# MedicalSheet.net
KiCad netlist of a schematic drawn in Altium Designer
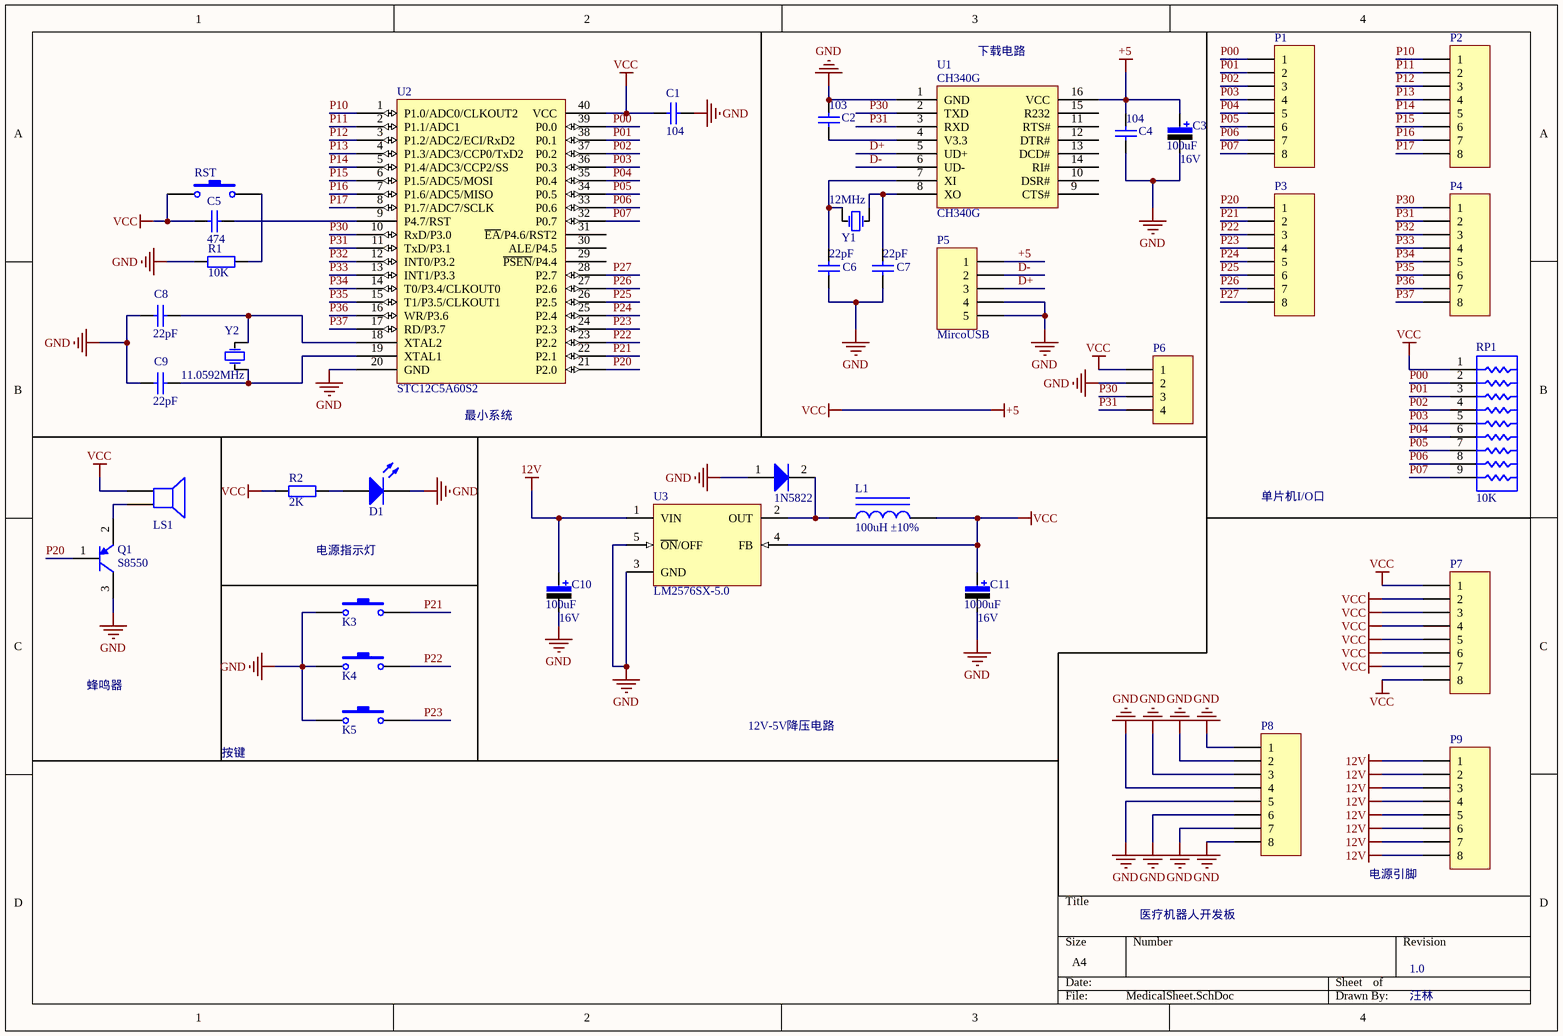
[diagram p0: MedicalSheet.SchDoc]

(export (version "E")
  (design (tool "Eeschema 10.0.6"))
  (components
    (comp (ref "1N5822")
      (value "Diode_SMA_S")
      (footprint "SMA(DO-214AC)_S1")
      (description "SMA")
      (libsource (lib "Miscellaneous_Devices_ZSF_Library") (part "Diode_SMA_S"))
    )
    (comp (ref "C1")
      (value "104")
      (footprint "C-RAD-0805")
      (description "无极性电容")
      (fields (field (name "Comment") "Cap") (field (name "PUBLISHER") "Altium Limited"))
      (libsource (lib "Fszhang") (part "Cap"))
    )
    (comp (ref "C2")
      (value "103")
      (footprint "C-RAD-0805")
      (description "无极性电容")
      (fields (field (name "Comment") "Cap") (field (name "PUBLISHER") "Altium Limited"))
      (libsource (lib "Fszhang") (part "Cap"))
    )
    (comp (ref "C3")
      (value "100uF")
      (footprint "C-RB-8")
      (description "极性电解电容")
      (fields
        (field (name "VOL") "16V")
        (field (name "Comment") "Cap Pol")
        (field (name "PUBLISHER") "Altium Limited")
      )
      (libsource (lib "Fszhang") (part "Cap Pol"))
    )
    (comp (ref "C4")
      (value "104")
      (footprint "C-RAD-0805")
      (description "无极性电容")
      (fields (field (name "Comment") "Cap") (field (name "PUBLISHER") "Altium Limited"))
      (libsource (lib "Fszhang") (part "Cap"))
    )
    (comp (ref "C5")
      (value "474")
      (footprint "C-RAD-0805")
      (description "无极性电容")
      (fields (field (name "Comment") "Cap") (field (name "PUBLISHER") "Altium Limited"))
      (libsource (lib "Fszhang") (part "Cap"))
    )
    (comp (ref "C6")
      (value "22pF")
      (footprint "C-RAD-0805")
      (description "无极性电容")
      (fields (field (name "Comment") "Cap") (field (name "PUBLISHER") "Altium Limited"))
      (libsource (lib "Fszhang") (part "Cap"))
    )
    (comp (ref "C7")
      (value "22pF")
      (footprint "C-RAD-0805")
      (description "无极性电容")
      (fields (field (name "Comment") "Cap") (field (name "PUBLISHER") "Altium Limited"))
      (libsource (lib "Fszhang") (part "Cap"))
    )
    (comp (ref "C8")
      (value "22pF")
      (footprint "C-RAD-0805")
      (description "无极性电容")
      (fields (field (name "Comment") "Cap") (field (name "PUBLISHER") "Altium Limited"))
      (libsource (lib "Fszhang") (part "Cap"))
    )
    (comp (ref "C9")
      (value "22pF")
      (footprint "C-RAD-0805")
      (description "无极性电容")
      (fields (field (name "Comment") "Cap") (field (name "PUBLISHER") "Altium Limited"))
      (libsource (lib "Fszhang") (part "Cap"))
    )
    (comp (ref "C10")
      (value "100uF")
      (footprint "C-RB-8")
      (description "极性电解电容")
      (fields
        (field (name "VOL") "16V")
        (field (name "Comment") "Cap Pol")
        (field (name "PUBLISHER") "Altium Limited")
      )
      (libsource (lib "Fszhang") (part "Cap Pol"))
    )
    (comp (ref "C11")
      (value "1000uF")
      (footprint "C-RB-8")
      (description "极性电解电容")
      (fields
        (field (name "VOL") "16V")
        (field (name "Comment") "Cap Pol")
        (field (name "PUBLISHER") "Altium Limited")
      )
      (libsource (lib "Fszhang") (part "Cap Pol"))
    )
    (comp (ref "D1")
      (value "LED0")
      (footprint "LED3")
      (description "发光二极管")
      (fields (field (name "PUBLISHER") "Altium Limited"))
      (libsource (lib "PCB_One") (part "LED0"))
    )
    (comp (ref "K3")
      (value "Switch1")
      (footprint "SW_PB - 6.5x4.5")
      (description "按键/单刀单掷开关")
      (libsource (lib "PCB_One") (part "Switch1"))
    )
    (comp (ref "K4")
      (value "Switch1")
      (footprint "SW_PB - 6.5x4.5")
      (description "按键/单刀单掷开关")
      (libsource (lib "PCB_One") (part "Switch1"))
    )
    (comp (ref "K5")
      (value "Switch1")
      (footprint "SW_PB - 6.5x4.5")
      (description "按键/单刀单掷开关")
      (libsource (lib "PCB_One") (part "Switch1"))
    )
    (comp (ref "L1")
      (value "100uH ±10%")
      (footprint "0805_L")
      (description "贴片电感")
      (libsource (lib "Miscellaneous_Devices_ZSF_Library") (part "0805 100uH 10%"))
    )
    (comp (ref "LS1") (value "SPEAKER") (footprint "Beep") (libsource (lib "PCB_One") (part "SPEAKER")))
    (comp (ref "P1")
      (value "Header 8")
      (footprint "SIP8 - duplicate")
      (description "8PIN")
      (libsource (lib "PCB_One") (part "Header 8"))
    )
    (comp (ref "P2")
      (value "Header 8")
      (footprint "SIP8 - duplicate")
      (description "8PIN")
      (libsource (lib "PCB_One") (part "Header 8"))
    )
    (comp (ref "P3")
      (value "Header 8")
      (footprint "SIP8 - duplicate")
      (description "8PIN")
      (libsource (lib "PCB_One") (part "Header 8"))
    )
    (comp (ref "P4")
      (value "Header 8")
      (footprint "SIP8 - duplicate")
      (description "8PIN")
      (libsource (lib "PCB_One") (part "Header 8"))
    )
    (comp (ref "P5")
      (value "MircoUSB")
      (footprint "MircoUSB")
      (description "5PIN")
      (libsource (lib "PCB_One") (part "Header 5"))
    )
    (comp (ref "P6")
      (value "Header 4")
      (footprint "HDR4X1_A")
      (description "接插件")
      (fields (field (name "PUBLISHER") "Altium Limited"))
      (libsource (lib "Fszhang") (part "Header 4"))
    )
    (comp (ref "P7")
      (value "Header 8")
      (footprint "SIP8 - duplicate")
      (description "8PIN")
      (libsource (lib "PCB_One") (part "Header 8"))
    )
    (comp (ref "P8")
      (value "Header 8")
      (footprint "SIP8 - duplicate")
      (description "8PIN")
      (libsource (lib "PCB_One") (part "Header 8"))
    )
    (comp (ref "P9")
      (value "Header 8")
      (footprint "SIP8 - duplicate")
      (description "8PIN")
      (libsource (lib "PCB_One") (part "Header 8"))
    )
    (comp (ref "Q1")
      (value "S8550")
      (footprint "SOT-23")
      (description "PNP贴片三极管")
      (fields (field (name "PUBLISHER") "Altium Limited"))
      (libsource (lib "Fszhang") (part "SS8550"))
    )
    (comp (ref "R1")
      (value "10K")
      (footprint "0805-1")
      (description "贴片电阻")
      (fields (field (name "Comment") "Res1") (field (name "PUBLISHER") "Altium Limited"))
      (libsource (lib "Fszhang") (part "Res1"))
    )
    (comp (ref "R2")
      (value "2K")
      (footprint "0805-1")
      (description "贴片电阻")
      (fields (field (name "Comment") "Res1") (field (name "PUBLISHER") "Altium Limited"))
      (libsource (lib "Fszhang") (part "Res1"))
    )
    (comp (ref "RP1")
      (value "10K")
      (footprint "SIP9 - duplicate")
      (description "9PIN排阻")
      (libsource (lib "PCB_One") (part "Res Pack2"))
    )
    (comp (ref "RST")
      (value "Switch1")
      (footprint "SW_PB - 6.5x4.5")
      (description "按键/单刀单掷开关")
      (libsource (lib "PCB_One") (part "Switch1"))
    )
    (comp (ref "U1")
      (value "CH340G")
      (footprint "SOIC-16_150mil")
      (description "USB")
      (libsource (lib "Miscellaneous_Devices_ZSF_Library") (part "CH340G"))
    )
    (comp (ref "U2")
      (value "STC12C5A60S2")
      (footprint "DIP-40")
      (description "STC12C5A60S2_DIP")
      (libsource (lib "Miscellaneous_Devices_ZSF_Library") (part "STC12C5A60S2_DIP"))
    )
    (comp (ref "U3")
      (value "LM2576SX-5.0")
      (footprint "TO-263-5")
      (description "DC-DC芯片")
      (libsource (lib "Miscellaneous_Devices_ZSF_Library") (part "LM2576SX-5.0"))
    )
    (comp (ref "Y1")
      (value "12MHz")
      (footprint "XTAL1")
      (description "晶振")
      (fields (field (name "Comment") "XTAL") (field (name "PUBLISHER") "Altium Limited"))
      (libsource (lib "PCB_One") (part "XTAL"))
    )
    (comp (ref "Y2")
      (value "11.0592MHz")
      (footprint "XTAL1")
      (description "晶振")
      (fields (field (name "Comment") "XTAL") (field (name "PUBLISHER") "Altium Limited"))
      (libsource (lib "PCB_One") (part "XTAL"))
    )
  )
  (nets
    (net (code "1") (name "+5") (class "Default")
      (node (ref "C1") (pin "1") (pinfunction "1_1") (pintype "passive"))
      (node (ref "C11") (pin "1") (pinfunction "1_1") (pintype "passive"))
      (node (ref "C3") (pin "1") (pinfunction "1_1") (pintype "passive"))
      (node (ref "C4") (pin "2") (pinfunction "2_2") (pintype "passive"))
      (node (ref "C5") (pin "1") (pinfunction "1_1") (pintype "passive"))
      (node (ref "L1") (pin "2") (pinfunction "2_2") (pintype "passive"))
      (node (ref "LS1") (pin "1") (pinfunction "1_1") (pintype "passive"))
      (node (ref "P5") (pin "1") (pinfunction "1_1") (pintype "passive"))
      (node (ref "P6") (pin "1") (pinfunction "1_1") (pintype "passive"))
      (node (ref "P7") (pin "1") (pinfunction "1_1") (pintype "passive"))
      (node (ref "P7") (pin "2") (pinfunction "2_2") (pintype "passive"))
      (node (ref "P7") (pin "3") (pinfunction "3_3") (pintype "passive"))
      (node (ref "P7") (pin "4") (pinfunction "4_4") (pintype "passive"))
      (node (ref "P7") (pin "5") (pinfunction "5_5") (pintype "passive"))
      (node (ref "P7") (pin "6") (pinfunction "6_6") (pintype "passive"))
      (node (ref "P7") (pin "7") (pinfunction "7_7") (pintype "passive"))
      (node (ref "P7") (pin "8") (pinfunction "8_8") (pintype "passive"))
      (node (ref "R2") (pin "1") (pinfunction "1_1") (pintype "passive"))
      (node (ref "RP1") (pin "1") (pinfunction "1_1") (pintype "passive"))
      (node (ref "RST") (pin "1") (pinfunction "1_1") (pintype "passive"))
      (node (ref "U1") (pin "16") (pinfunction "VCC_16") (pintype "passive"))
      (node (ref "U2") (pin "40") (pinfunction "VCC_40") (pintype "power_in"))
      (node (ref "U3") (pin "4") (pinfunction "FB_4") (pintype "input"))
    )
    (net (code "2") (name "/D+") (class "Default")
      (node (ref "P5") (pin "3") (pinfunction "3_3") (pintype "passive"))
      (node (ref "U1") (pin "5") (pinfunction "UD+_5") (pintype "passive"))
    )
    (net (code "3") (name "/D-") (class "Default")
      (node (ref "P5") (pin "2") (pinfunction "2_2") (pintype "passive"))
      (node (ref "U1") (pin "6") (pinfunction "UD-_6") (pintype "passive"))
    )
    (net (code "4") (name "/P00") (class "Default")
      (node (ref "P1") (pin "1") (pinfunction "1_1") (pintype "passive"))
      (node (ref "RP1") (pin "2") (pinfunction "2_2") (pintype "passive"))
      (node (ref "U2") (pin "39") (pinfunction "P0.0_39") (pintype "bidirectional"))
    )
    (net (code "5") (name "/P01") (class "Default")
      (node (ref "P1") (pin "2") (pinfunction "2_2") (pintype "passive"))
      (node (ref "RP1") (pin "3") (pinfunction "3_3") (pintype "passive"))
      (node (ref "U2") (pin "38") (pinfunction "P0.1_38") (pintype "bidirectional"))
    )
    (net (code "6") (name "/P02") (class "Default")
      (node (ref "P1") (pin "3") (pinfunction "3_3") (pintype "passive"))
      (node (ref "RP1") (pin "4") (pinfunction "4_4") (pintype "passive"))
      (node (ref "U2") (pin "37") (pinfunction "P0.2_37") (pintype "bidirectional"))
    )
    (net (code "7") (name "/P03") (class "Default")
      (node (ref "P1") (pin "4") (pinfunction "4_4") (pintype "passive"))
      (node (ref "RP1") (pin "5") (pinfunction "5_5") (pintype "passive"))
      (node (ref "U2") (pin "36") (pinfunction "P0.3_36") (pintype "bidirectional"))
    )
    (net (code "8") (name "/P04") (class "Default")
      (node (ref "P1") (pin "5") (pinfunction "5_5") (pintype "passive"))
      (node (ref "RP1") (pin "6") (pinfunction "6_6") (pintype "passive"))
      (node (ref "U2") (pin "35") (pinfunction "P0.4_35") (pintype "bidirectional"))
    )
    (net (code "9") (name "/P05") (class "Default")
      (node (ref "P1") (pin "6") (pinfunction "6_6") (pintype "passive"))
      (node (ref "RP1") (pin "7") (pinfunction "7_7") (pintype "passive"))
      (node (ref "U2") (pin "34") (pinfunction "P0.5_34") (pintype "bidirectional"))
    )
    (net (code "10") (name "/P06") (class "Default")
      (node (ref "P1") (pin "7") (pinfunction "7_7") (pintype "passive"))
      (node (ref "RP1") (pin "8") (pinfunction "8_8") (pintype "passive"))
      (node (ref "U2") (pin "33") (pinfunction "P0.6_33") (pintype "bidirectional"))
    )
    (net (code "11") (name "/P07") (class "Default")
      (node (ref "P1") (pin "8") (pinfunction "8_8") (pintype "passive"))
      (node (ref "RP1") (pin "9") (pinfunction "9_9") (pintype "passive"))
      (node (ref "U2") (pin "32") (pinfunction "P0.7_32") (pintype "bidirectional"))
    )
    (net (code "12") (name "/P10") (class "Default")
      (node (ref "P2") (pin "1") (pinfunction "1_1") (pintype "passive"))
      (node (ref "U2") (pin "1") (pinfunction "P1.0/ADC0/CLKOUT2_1") (pintype "bidirectional"))
    )
    (net (code "13") (name "/P11") (class "Default")
      (node (ref "P2") (pin "2") (pinfunction "2_2") (pintype "passive"))
      (node (ref "U2") (pin "2") (pinfunction "P1.1/ADC1_2") (pintype "bidirectional"))
    )
    (net (code "14") (name "/P12") (class "Default")
      (node (ref "P2") (pin "3") (pinfunction "3_3") (pintype "passive"))
      (node (ref "U2") (pin "3") (pinfunction "P1.2/ADC2/ECI/RxD2_3") (pintype "bidirectional"))
    )
    (net (code "15") (name "/P13") (class "Default")
      (node (ref "P2") (pin "4") (pinfunction "4_4") (pintype "passive"))
      (node (ref "U2") (pin "4") (pinfunction "P1.3/ADC3/CCP0/TxD2_4") (pintype "bidirectional"))
    )
    (net (code "16") (name "/P14") (class "Default")
      (node (ref "P2") (pin "5") (pinfunction "5_5") (pintype "passive"))
      (node (ref "U2") (pin "5") (pinfunction "P1.4/ADC3/CCP2/SS_5") (pintype "bidirectional"))
    )
    (net (code "17") (name "/P15") (class "Default")
      (node (ref "P2") (pin "6") (pinfunction "6_6") (pintype "passive"))
      (node (ref "U2") (pin "6") (pinfunction "P1.5/ADC5/MOSI_6") (pintype "bidirectional"))
    )
    (net (code "18") (name "/P16") (class "Default")
      (node (ref "P2") (pin "7") (pinfunction "7_7") (pintype "passive"))
      (node (ref "U2") (pin "7") (pinfunction "P1.6/ADC5/MISO_7") (pintype "bidirectional"))
    )
    (net (code "19") (name "/P17") (class "Default")
      (node (ref "P2") (pin "8") (pinfunction "8_8") (pintype "passive"))
      (node (ref "U2") (pin "8") (pinfunction "P1.7/ADC7/SCLK_8") (pintype "bidirectional"))
    )
    (net (code "20") (name "/P20") (class "Default")
      (node (ref "P3") (pin "1") (pinfunction "1_1") (pintype "passive"))
      (node (ref "Q1") (pin "1") (pinfunction "B_1") (pintype "passive"))
      (node (ref "U2") (pin "21") (pinfunction "P2.0_21") (pintype "bidirectional"))
    )
    (net (code "21") (name "/P21") (class "Default")
      (node (ref "K3") (pin "2") (pinfunction "2_2") (pintype "passive"))
      (node (ref "P3") (pin "2") (pinfunction "2_2") (pintype "passive"))
      (node (ref "U2") (pin "22") (pinfunction "P2.1_22") (pintype "bidirectional"))
    )
    (net (code "22") (name "/P22") (class "Default")
      (node (ref "K4") (pin "2") (pinfunction "2_2") (pintype "passive"))
      (node (ref "P3") (pin "3") (pinfunction "3_3") (pintype "passive"))
      (node (ref "U2") (pin "23") (pinfunction "P2.2_23") (pintype "bidirectional"))
    )
    (net (code "23") (name "/P23") (class "Default")
      (node (ref "K5") (pin "2") (pinfunction "2_2") (pintype "passive"))
      (node (ref "P3") (pin "4") (pinfunction "4_4") (pintype "passive"))
      (node (ref "U2") (pin "24") (pinfunction "P2.3_24") (pintype "bidirectional"))
    )
    (net (code "24") (name "/P24") (class "Default")
      (node (ref "P3") (pin "5") (pinfunction "5_5") (pintype "passive"))
      (node (ref "U2") (pin "25") (pinfunction "P2.4_25") (pintype "bidirectional"))
    )
    (net (code "25") (name "/P25") (class "Default")
      (node (ref "P3") (pin "6") (pinfunction "6_6") (pintype "passive"))
      (node (ref "U2") (pin "26") (pinfunction "P2.5_26") (pintype "bidirectional"))
    )
    (net (code "26") (name "/P26") (class "Default")
      (node (ref "P3") (pin "7") (pinfunction "7_7") (pintype "passive"))
      (node (ref "U2") (pin "27") (pinfunction "P2.6_27") (pintype "bidirectional"))
    )
    (net (code "27") (name "/P27") (class "Default")
      (node (ref "P3") (pin "8") (pinfunction "8_8") (pintype "passive"))
      (node (ref "U2") (pin "28") (pinfunction "P2.7_28") (pintype "bidirectional"))
    )
    (net (code "28") (name "/P30") (class "Default")
      (node (ref "P4") (pin "1") (pinfunction "1_1") (pintype "passive"))
      (node (ref "P6") (pin "3") (pinfunction "3_3") (pintype "passive"))
      (node (ref "U1") (pin "2") (pinfunction "TXD_2") (pintype "passive"))
      (node (ref "U2") (pin "10") (pinfunction "RxD/P3.0_10") (pintype "bidirectional"))
    )
    (net (code "29") (name "/P31") (class "Default")
      (node (ref "P4") (pin "2") (pinfunction "2_2") (pintype "passive"))
      (node (ref "P6") (pin "4") (pinfunction "4_4") (pintype "passive"))
      (node (ref "U1") (pin "3") (pinfunction "RXD_3") (pintype "passive"))
      (node (ref "U2") (pin "11") (pinfunction "TxD/P3.1_11") (pintype "bidirectional"))
    )
    (net (code "30") (name "/P32") (class "Default")
      (node (ref "P4") (pin "3") (pinfunction "3_3") (pintype "passive"))
      (node (ref "U2") (pin "12") (pinfunction "INT0/P3.2_12") (pintype "bidirectional"))
    )
    (net (code "31") (name "/P33") (class "Default")
      (node (ref "P4") (pin "4") (pinfunction "4_4") (pintype "passive"))
      (node (ref "U2") (pin "13") (pinfunction "INT1/P3.3_13") (pintype "bidirectional"))
    )
    (net (code "32") (name "/P34") (class "Default")
      (node (ref "P4") (pin "5") (pinfunction "5_5") (pintype "passive"))
      (node (ref "U2") (pin "14") (pinfunction "T0/P3.4/CLKOUT0_14") (pintype "bidirectional"))
    )
    (net (code "33") (name "/P35") (class "Default")
      (node (ref "P4") (pin "6") (pinfunction "6_6") (pintype "passive"))
      (node (ref "U2") (pin "15") (pinfunction "T1/P3.5/CLKOUT1_15") (pintype "bidirectional"))
    )
    (net (code "34") (name "/P36") (class "Default")
      (node (ref "P4") (pin "7") (pinfunction "7_7") (pintype "passive"))
      (node (ref "U2") (pin "16") (pinfunction "WR/P3.6_16") (pintype "bidirectional"))
    )
    (net (code "35") (name "/P37") (class "Default")
      (node (ref "P4") (pin "8") (pinfunction "8_8") (pintype "passive"))
      (node (ref "U2") (pin "17") (pinfunction "RD/P3.7_17") (pintype "bidirectional"))
    )
    (net (code "36") (name "12V") (class "Default")
      (node (ref "C10") (pin "1") (pinfunction "1_1") (pintype "passive"))
      (node (ref "P9") (pin "1") (pinfunction "1_1") (pintype "passive"))
      (node (ref "P9") (pin "2") (pinfunction "2_2") (pintype "passive"))
      (node (ref "P9") (pin "3") (pinfunction "3_3") (pintype "passive"))
      (node (ref "P9") (pin "4") (pinfunction "4_4") (pintype "passive"))
      (node (ref "P9") (pin "5") (pinfunction "5_5") (pintype "passive"))
      (node (ref "P9") (pin "6") (pinfunction "6_6") (pintype "passive"))
      (node (ref "P9") (pin "7") (pinfunction "7_7") (pintype "passive"))
      (node (ref "P9") (pin "8") (pinfunction "8_8") (pintype "passive"))
      (node (ref "U3") (pin "1") (pinfunction "VIN_1") (pintype "power_in"))
    )
    (net (code "37") (name "GND") (class "Default")
      (node (ref "1N5822") (pin "1") (pinfunction "A_1") (pintype "passive"))
      (node (ref "C1") (pin "2") (pinfunction "2_2") (pintype "passive"))
      (node (ref "C10") (pin "2") (pinfunction "2_2") (pintype "passive"))
      (node (ref "C11") (pin "2") (pinfunction "2_2") (pintype "passive"))
      (node (ref "C2") (pin "2") (pinfunction "2_2") (pintype "passive"))
      (node (ref "C3") (pin "2") (pinfunction "2_2") (pintype "passive"))
      (node (ref "C4") (pin "1") (pinfunction "1_1") (pintype "passive"))
      (node (ref "C6") (pin "1") (pinfunction "1_1") (pintype "passive"))
      (node (ref "C7") (pin "1") (pinfunction "1_1") (pintype "passive"))
      (node (ref "C8") (pin "1") (pinfunction "1_1") (pintype "passive"))
      (node (ref "C9") (pin "1") (pinfunction "1_1") (pintype "passive"))
      (node (ref "D1") (pin "K") (pinfunction "K_K") (pintype "passive"))
      (node (ref "K3") (pin "1") (pinfunction "1_1") (pintype "passive"))
      (node (ref "K4") (pin "1") (pinfunction "1_1") (pintype "passive"))
      (node (ref "K5") (pin "1") (pinfunction "1_1") (pintype "passive"))
      (node (ref "P5") (pin "4") (pinfunction "4_4") (pintype "passive"))
      (node (ref "P5") (pin "5") (pinfunction "5_5") (pintype "passive"))
      (node (ref "P6") (pin "2") (pinfunction "2_2") (pintype "passive"))
      (node (ref "P8") (pin "1") (pinfunction "1_1") (pintype "passive"))
      (node (ref "P8") (pin "2") (pinfunction "2_2") (pintype "passive"))
      (node (ref "P8") (pin "3") (pinfunction "3_3") (pintype "passive"))
      (node (ref "P8") (pin "4") (pinfunction "4_4") (pintype "passive"))
      (node (ref "P8") (pin "5") (pinfunction "5_5") (pintype "passive"))
      (node (ref "P8") (pin "6") (pinfunction "6_6") (pintype "passive"))
      (node (ref "P8") (pin "7") (pinfunction "7_7") (pintype "passive"))
      (node (ref "P8") (pin "8") (pinfunction "8_8") (pintype "passive"))
      (node (ref "Q1") (pin "3") (pinfunction "C_3") (pintype "passive"))
      (node (ref "R1") (pin "1") (pinfunction "1_1") (pintype "passive"))
      (node (ref "U1") (pin "1") (pinfunction "GND_1") (pintype "passive"))
      (node (ref "U2") (pin "20") (pinfunction "GND_20") (pintype "power_in"))
      (node (ref "U3") (pin "3") (pinfunction "GND_3") (pintype "power_in"))
      (node (ref "U3") (pin "5") (pinfunction "~{ON}/OFF_5") (pintype "input"))
    )
    (net (code "38") (name "Net-(1N5822-K)") (class "Default")
      (node (ref "1N5822") (pin "2") (pinfunction "K_2") (pintype "passive"))
      (node (ref "L1") (pin "1") (pinfunction "1_1") (pintype "passive"))
      (node (ref "U3") (pin "2") (pinfunction "OUT_2") (pintype "power_in"))
    )
    (net (code "39") (name "Net-(D1-PadA)") (class "Default")
      (node (ref "D1") (pin "A") (pinfunction "A_A") (pintype "passive"))
      (node (ref "R2") (pin "2") (pinfunction "2_2") (pintype "passive"))
    )
    (net (code "40") (name "Net-(Q1-E)") (class "Default")
      (node (ref "LS1") (pin "2") (pinfunction "2_2") (pintype "passive"))
      (node (ref "Q1") (pin "2") (pinfunction "E_2") (pintype "passive"))
    )
    (net (code "41") (name "Net-(R1-Pad2)") (class "Default")
      (node (ref "R1") (pin "2") (pinfunction "2_2") (pintype "passive"))
      (node (ref "RST") (pin "2") (pinfunction "2_2") (pintype "passive"))
    )
    (net (code "42") (name "Net-(U1-V3.3)") (class "Default")
      (node (ref "C2") (pin "1") (pinfunction "1_1") (pintype "passive"))
      (node (ref "U1") (pin "4") (pinfunction "V3.3_4") (pintype "passive"))
    )
    (net (code "43") (name "Net-(U1-XI)") (class "Default")
      (node (ref "C6") (pin "2") (pinfunction "2_2") (pintype "passive"))
      (node (ref "U1") (pin "7") (pinfunction "XI_7") (pintype "passive"))
      (node (ref "Y1") (pin "2") (pinfunction "OSC2_2") (pintype "passive"))
    )
    (net (code "44") (name "Net-(U1-XO)") (class "Default")
      (node (ref "C7") (pin "2") (pinfunction "2_2") (pintype "passive"))
      (node (ref "U1") (pin "8") (pinfunction "XO_8") (pintype "passive"))
      (node (ref "Y1") (pin "1") (pinfunction "OSC1_1") (pintype "passive"))
    )
    (net (code "45") (name "Net-(U2-P4.7{slash}RST)") (class "Default")
      (node (ref "C5") (pin "2") (pinfunction "2_2") (pintype "passive"))
      (node (ref "U2") (pin "9") (pinfunction "P4.7/RST_9") (pintype "passive"))
    )
    (net (code "46") (name "Net-(U2-XTAL1)") (class "Default")
      (node (ref "C9") (pin "2") (pinfunction "2_2") (pintype "passive"))
      (node (ref "U2") (pin "19") (pinfunction "XTAL1_19") (pintype "passive"))
      (node (ref "Y2") (pin "1") (pinfunction "OSC1_1") (pintype "passive"))
    )
    (net (code "47") (name "Net-(U2-XTAL2)") (class "Default")
      (node (ref "C8") (pin "2") (pinfunction "2_2") (pintype "passive"))
      (node (ref "U2") (pin "18") (pinfunction "XTAL2_18") (pintype "passive"))
      (node (ref "Y2") (pin "2") (pinfunction "OSC2_2") (pintype "passive"))
    )
    (net (code "48") (name "unconnected-(U1-CTS#-Pad9)") (class "Default")
      (node (ref "U1") (pin "9") (pinfunction "CTS#_9") (pintype "passive"))
    )
    (net (code "49") (name "unconnected-(U1-DCD#-Pad13)") (class "Default")
      (node (ref "U1") (pin "13") (pinfunction "DCD#_13") (pintype "passive"))
    )
    (net (code "50") (name "unconnected-(U1-DSR#-Pad10)") (class "Default")
      (node (ref "U1") (pin "10") (pinfunction "DSR#_10") (pintype "passive"))
    )
    (net (code "51") (name "unconnected-(U1-DTR#-Pad12)") (class "Default")
      (node (ref "U1") (pin "12") (pinfunction "DTR#_12") (pintype "passive"))
    )
    (net (code "52") (name "unconnected-(U1-R232-Pad15)") (class "Default")
      (node (ref "U1") (pin "15") (pinfunction "R232_15") (pintype "passive"))
    )
    (net (code "53") (name "unconnected-(U1-RI#-Pad14)") (class "Default")
      (node (ref "U1") (pin "14") (pinfunction "RI#_14") (pintype "passive"))
    )
    (net (code "54") (name "unconnected-(U1-RTS#-Pad11)") (class "Default")
      (node (ref "U1") (pin "11") (pinfunction "RTS#_11") (pintype "passive"))
    )
    (net (code "55") (name "unconnected-(U2-ALE{slash}P4.5-Pad30)") (class "Default")
      (node (ref "U2") (pin "30") (pinfunction "ALE/P4.5_30") (pintype "passive"))
    )
    (net (code "56") (name "unconnected-(U2-~{EA}{slash}P4.6{slash}RST2-Pad31)") (class "Default")
      (node (ref "U2") (pin "31") (pinfunction "~{EA}/P4.6/RST2_31") (pintype "passive"))
    )
    (net (code "57") (name "unconnected-(U2-~{PSEN}{slash}P4.4-Pad29)") (class "Default")
      (node (ref "U2") (pin "29") (pinfunction "~{PSEN}/P4.4_29") (pintype "passive"))
    )
  )
)
